# Smart_Driver.net
KiCad netlist of a schematic drawn in Altium Designer
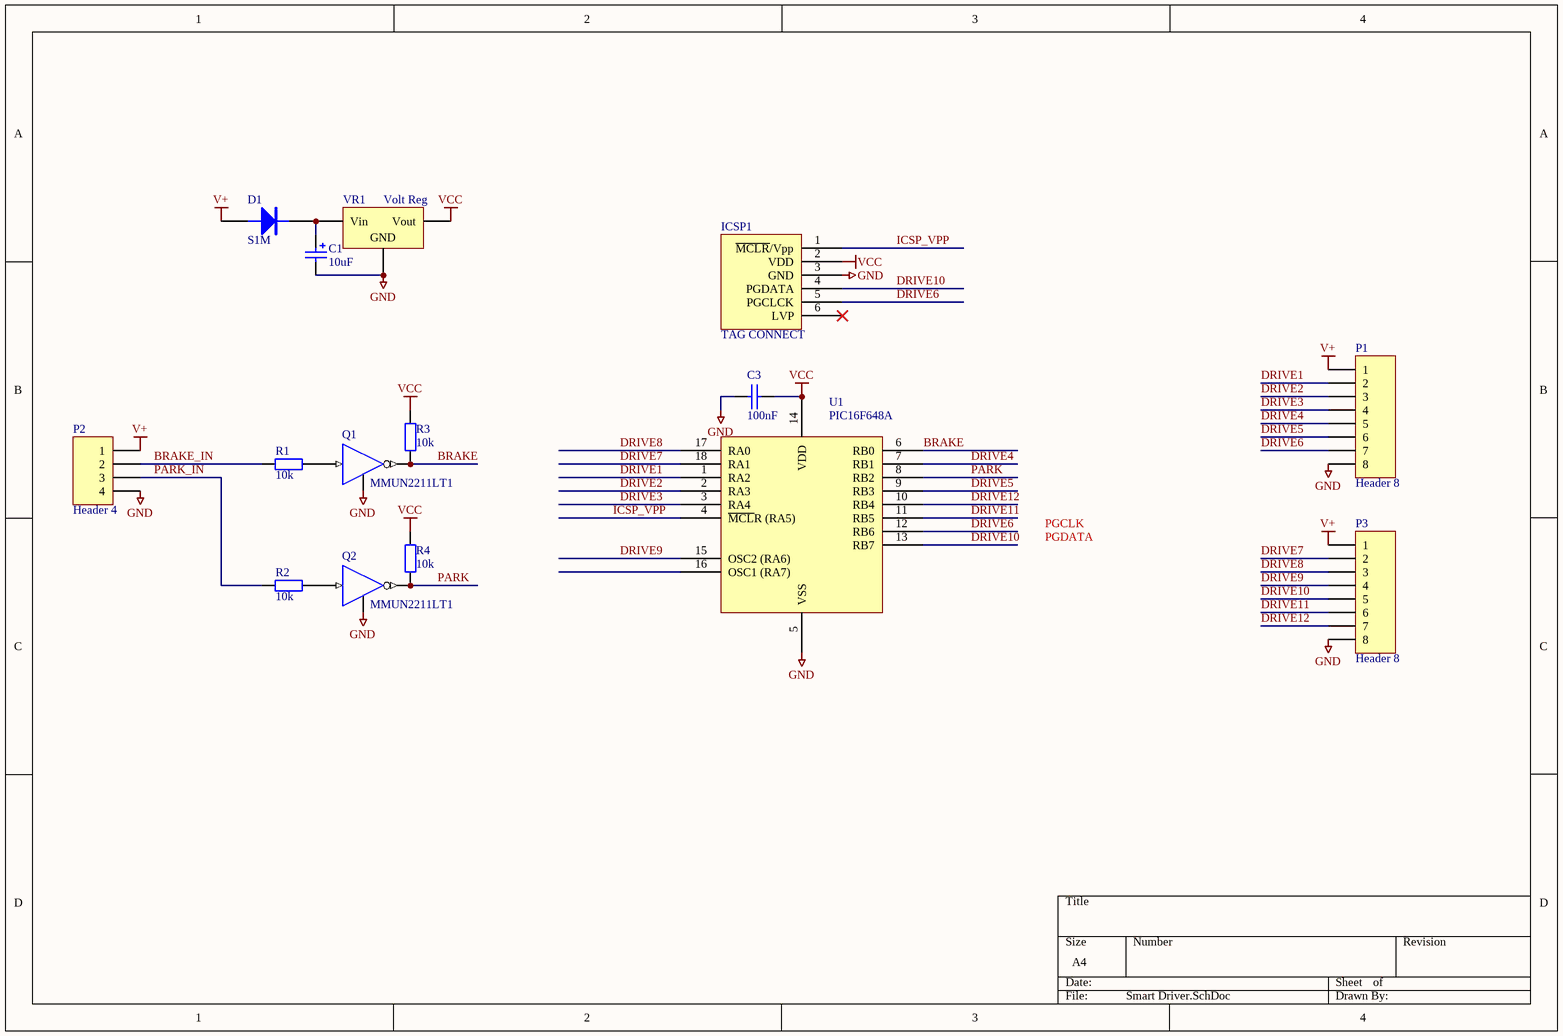
[diagram p0: Smart Driver.SchDoc]

(export (version "E")
  (design (tool "Eeschema 10.0.6"))
  (components
    (comp (ref "C1")
      (value "10uF")
      (footprint "CAP ELECTRO SIZE-C")
      (description "CAPACITOR POLARISED TAG B CASE")
      (fields
        (field (name "MANUFACTURER") "Cornell Dubilier")
        (field (name "MOUSER PART NO.") "598-AVE106M25C12T-F")
      )
      (libsource (lib "Mi-Call Schematic") (part "Cap Pol"))
    )
    (comp (ref "C3")
      (value "100nF")
      (footprint "CAP (3D) - 0805")
      (description "CAPACITOR SMD 0402")
      (libsource (lib "401 CCPA") (part "CAP"))
    )
    (comp (ref "D1")
      (value "S1M")
      (footprint "DO-214AC")
      (description "DIODE, POWER")
      (fields (field (name "MOUSER PART NO.") "821-S1M") (field (name "MANUFACTURER") "TAIWAN SEMI"))
      (libsource (lib "*") (part "DIODE"))
    )
    (comp (ref "ICSP1")
      (value "TAG CONNECT")
      (footprint "ICSP - TAG CONNECT TYPE2")
      (fields (field (name "MANUFACTURER") "N/A - PCB ARTWORK"))
      (libsource (lib "I2C PENDANT") (part "ICSP - TAG CONNECT"))
    )
    (comp (ref "P1")
      (value "Header 8")
      (footprint "HDR1X8")
      (description "Header, 8-Pin")
      (fields (field (name "PUBLISHER") "Altium Limited"))
      (libsource (lib "Miscellaneous Connectors") (part "Header 8"))
    )
    (comp (ref "P2")
      (value "Header 4")
      (footprint "HDR1X4")
      (description "Header, 4-Pin")
      (fields (field (name "PUBLISHER") "Altium Limited"))
      (libsource (lib "Miscellaneous Connectors") (part "Header 4"))
    )
    (comp (ref "P3")
      (value "Header 8")
      (footprint "HDR1X8")
      (description "Header, 8-Pin")
      (fields (field (name "PUBLISHER") "Altium Limited"))
      (libsource (lib "Miscellaneous Connectors") (part "Header 8"))
    )
    (comp (ref "Q1")
      (value "MMUN2211LT1")
      (footprint "SOT23-3L")
      (fields
        (field (name "MOUSER PART NO.") "863-MMUN2211LT1G")
        (field (name "MANUFACTURER") "ON Semiconductor")
        (field (name "MANUFACTURER PART NO.") "MMUN2211LT1G")
      )
      (libsource (lib "401 CCPA") (part "NPN DIGITAL TRANSISTOR"))
    )
    (comp (ref "Q2")
      (value "MMUN2211LT1")
      (footprint "SOT23-3L")
      (fields
        (field (name "MOUSER PART NO.") "863-MMUN2211LT1G")
        (field (name "MANUFACTURER") "ON Semiconductor")
        (field (name "MANUFACTURER PART NO.") "MMUN2211LT1G")
      )
      (libsource (lib "401 CCPA") (part "NPN DIGITAL TRANSISTOR"))
    )
    (comp (ref "R1")
      (value "10k")
      (footprint "RES (3D) - 0805")
      (description "Resistor")
      (fields (field (name "Comment") "Res2"))
      (libsource (lib "") (part "Res2_1"))
    )
    (comp (ref "R2")
      (value "10k")
      (footprint "RES (3D) - 0805")
      (description "Resistor")
      (fields (field (name "Comment") "Res2"))
      (libsource (lib "") (part "Res2_1"))
    )
    (comp (ref "R3")
      (value "10k")
      (footprint "RES (3D) - 0805")
      (description "Resistor")
      (fields (field (name "Comment") "Res2"))
      (libsource (lib "Miscellaneous Devices") (part "Res2"))
    )
    (comp (ref "R4")
      (value "10k")
      (footprint "RES (3D) - 0805")
      (description "Resistor")
      (fields (field (name "Comment") "Res2"))
      (libsource (lib "Miscellaneous Devices") (part "Res2"))
    )
    (comp (ref "U1")
      (value "PIC16F648A")
      (footprint "SOIC-18")
      (description "PIC16F88")
      (fields
        (field (name "MOUSER PART NO.") "579-PIC16F88-E/SS")
        (field (name "FARNELL PART NO.") "9761519")
      )
      (libsource (lib "NASCO") (part "PIC16F87/88"))
    )
    (comp (ref "VR1")
      (value "Volt Reg")
      (footprint "SOT89")
      (description "Voltage Regulator")
      (libsource (lib "Miscellaneous Devices") (part "Volt Reg"))
    )
  )
  (nets
    (net (code "1") (name "/BRAKE") (class "Default")
      (node (ref "Q1") (pin "3") (pinfunction "C_3") (pintype "output"))
      (node (ref "R3") (pin "1") (pinfunction "1_1") (pintype "passive"))
      (node (ref "U1") (pin "6") (pinfunction "RB0_6") (pintype "passive"))
    )
    (net (code "2") (name "/BRAKE_IN") (class "Default")
      (node (ref "P2") (pin "2") (pinfunction "2_2") (pintype "passive"))
      (node (ref "R1") (pin "2") (pinfunction "2_2") (pintype "passive"))
    )
    (net (code "3") (name "/DRIVE1") (class "Default")
      (node (ref "P1") (pin "2") (pinfunction "2_2") (pintype "passive"))
      (node (ref "U1") (pin "1") (pinfunction "RA2_1") (pintype "passive"))
    )
    (net (code "4") (name "/DRIVE2") (class "Default")
      (node (ref "P1") (pin "3") (pinfunction "3_3") (pintype "passive"))
      (node (ref "U1") (pin "2") (pinfunction "RA3_2") (pintype "passive"))
    )
    (net (code "5") (name "/DRIVE3") (class "Default")
      (node (ref "P1") (pin "4") (pinfunction "4_4") (pintype "passive"))
      (node (ref "U1") (pin "3") (pinfunction "RA4_3") (pintype "passive"))
    )
    (net (code "6") (name "/DRIVE4") (class "Default")
      (node (ref "P1") (pin "5") (pinfunction "5_5") (pintype "passive"))
      (node (ref "U1") (pin "7") (pinfunction "RB1_7") (pintype "passive"))
    )
    (net (code "7") (name "/DRIVE5") (class "Default")
      (node (ref "P1") (pin "6") (pinfunction "6_6") (pintype "passive"))
      (node (ref "U1") (pin "9") (pinfunction "RB3_9") (pintype "passive"))
    )
    (net (code "8") (name "/DRIVE6") (class "Default")
      (node (ref "ICSP1") (pin "5") (pinfunction "PGCLCK_5") (pintype "passive"))
      (node (ref "P1") (pin "7") (pinfunction "7_7") (pintype "passive"))
      (node (ref "U1") (pin "12") (pinfunction "RB6_12") (pintype "passive"))
    )
    (net (code "9") (name "/DRIVE7") (class "Default")
      (node (ref "P3") (pin "2") (pinfunction "2_2") (pintype "passive"))
      (node (ref "U1") (pin "18") (pinfunction "RA1_18") (pintype "passive"))
    )
    (net (code "10") (name "/DRIVE8") (class "Default")
      (node (ref "P3") (pin "3") (pinfunction "3_3") (pintype "passive"))
      (node (ref "U1") (pin "17") (pinfunction "RA0_17") (pintype "passive"))
    )
    (net (code "11") (name "/DRIVE9") (class "Default")
      (node (ref "P3") (pin "4") (pinfunction "4_4") (pintype "passive"))
      (node (ref "U1") (pin "15") (pinfunction "OSC2_(RA6)_15") (pintype "passive"))
    )
    (net (code "12") (name "/DRIVE10") (class "Default")
      (node (ref "ICSP1") (pin "4") (pinfunction "PGDATA_4") (pintype "passive"))
      (node (ref "P3") (pin "5") (pinfunction "5_5") (pintype "passive"))
      (node (ref "U1") (pin "13") (pinfunction "RB7_13") (pintype "passive"))
    )
    (net (code "13") (name "/DRIVE11") (class "Default")
      (node (ref "P3") (pin "6") (pinfunction "6_6") (pintype "passive"))
      (node (ref "U1") (pin "11") (pinfunction "RB5_11") (pintype "passive"))
    )
    (net (code "14") (name "/DRIVE12") (class "Default")
      (node (ref "P3") (pin "7") (pinfunction "7_7") (pintype "passive"))
      (node (ref "U1") (pin "10") (pinfunction "RB4_10") (pintype "passive"))
    )
    (net (code "15") (name "/ICSP_VPP") (class "Default")
      (node (ref "ICSP1") (pin "1") (pinfunction "~{MCLR}/Vpp_1") (pintype "passive"))
      (node (ref "U1") (pin "4") (pinfunction "~{MCL}R_(RA5)_4") (pintype "passive"))
    )
    (net (code "16") (name "/PARK") (class "Default")
      (node (ref "Q2") (pin "3") (pinfunction "C_3") (pintype "output"))
      (node (ref "R4") (pin "1") (pinfunction "1_1") (pintype "passive"))
      (node (ref "U1") (pin "8") (pinfunction "RB2_8") (pintype "passive"))
    )
    (net (code "17") (name "/PARK_IN") (class "Default")
      (node (ref "P2") (pin "3") (pinfunction "3_3") (pintype "passive"))
      (node (ref "R2") (pin "2") (pinfunction "2_2") (pintype "passive"))
    )
    (net (code "18") (name "GND") (class "Default")
      (node (ref "C1") (pin "2") (pinfunction "2_2") (pintype "passive"))
      (node (ref "C3") (pin "1") (pinfunction "1_1") (pintype "passive"))
      (node (ref "ICSP1") (pin "3") (pinfunction "GND_3") (pintype "passive"))
      (node (ref "P1") (pin "8") (pinfunction "8_8") (pintype "passive"))
      (node (ref "P2") (pin "4") (pinfunction "4_4") (pintype "passive"))
      (node (ref "P3") (pin "8") (pinfunction "8_8") (pintype "passive"))
      (node (ref "Q1") (pin "2") (pinfunction "E_2") (pintype "passive"))
      (node (ref "Q2") (pin "2") (pinfunction "E_2") (pintype "passive"))
      (node (ref "U1") (pin "5") (pinfunction "VSS_5") (pintype "passive"))
      (node (ref "VR1") (pin "2") (pinfunction "GND_2") (pintype "passive"))
    )
    (net (code "19") (name "Net-(D1-K)") (class "Default")
      (node (ref "C1") (pin "1") (pinfunction "1_1") (pintype "passive"))
      (node (ref "D1") (pin "2") (pinfunction "K_2") (pintype "passive"))
      (node (ref "VR1") (pin "1") (pinfunction "Vin_1") (pintype "passive"))
    )
    (net (code "20") (name "Net-(Q1-B)") (class "Default")
      (node (ref "Q1") (pin "1") (pinfunction "B_1") (pintype "input"))
      (node (ref "R1") (pin "1") (pinfunction "1_1") (pintype "passive"))
    )
    (net (code "21") (name "Net-(Q2-B)") (class "Default")
      (node (ref "Q2") (pin "1") (pinfunction "B_1") (pintype "input"))
      (node (ref "R2") (pin "1") (pinfunction "1_1") (pintype "passive"))
    )
    (net (code "22") (name "V+") (class "Default")
      (node (ref "D1") (pin "1") (pinfunction "A_1") (pintype "passive"))
      (node (ref "P1") (pin "1") (pinfunction "1_1") (pintype "passive"))
      (node (ref "P2") (pin "1") (pinfunction "1_1") (pintype "passive"))
      (node (ref "P3") (pin "1") (pinfunction "1_1") (pintype "passive"))
    )
    (net (code "23") (name "VCC") (class "Default")
      (node (ref "C3") (pin "2") (pinfunction "2_2") (pintype "passive"))
      (node (ref "ICSP1") (pin "2") (pinfunction "VDD_2") (pintype "passive"))
      (node (ref "R3") (pin "2") (pinfunction "2_2") (pintype "passive"))
      (node (ref "R4") (pin "2") (pinfunction "2_2") (pintype "passive"))
      (node (ref "U1") (pin "14") (pinfunction "VDD_14") (pintype "passive"))
      (node (ref "VR1") (pin "3") (pinfunction "Vout_3") (pintype "passive"))
    )
    (net (code "24") (name "unconnected-(ICSP1-LVP-Pad6)") (class "Default")
      (node (ref "ICSP1") (pin "6") (pinfunction "LVP_6") (pintype "passive+no_connect"))
    )
    (net (code "25") (name "unconnected-(U1-OSC1_(RA7)-Pad16)") (class "Default")
      (node (ref "U1") (pin "16") (pinfunction "OSC1_(RA7)_16") (pintype "passive"))
    )
  )
)
